# Drive.net
KiCad netlist of a schematic drawn in Altium Designer
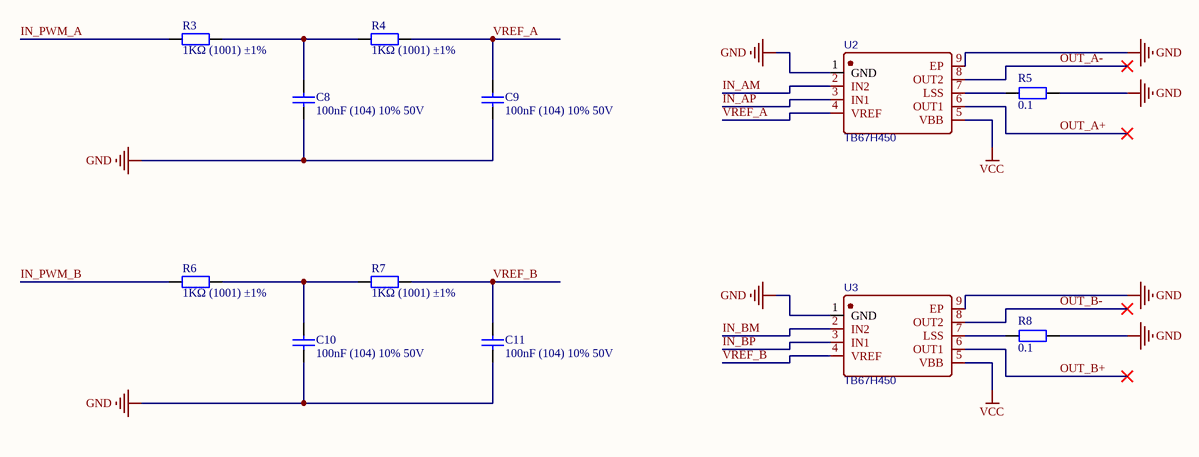
[diagram p0: Drive.SchDoc]

(export (version "E")
  (design (tool "Eeschema 10.0.6"))
  (components
    (comp (ref "C8")
      (value "100nF (104) 10% 50V")
      (footprint "0603_C")
      (description "贴片电容")
      (libsource (lib "X_Drive") (part "0603 100nF (104) 10% 50V"))
    )
    (comp (ref "C9")
      (value "100nF (104) 10% 50V")
      (footprint "0603_C")
      (description "贴片电容")
      (libsource (lib "X_Drive") (part "0603 100nF (104) 10% 50V"))
    )
    (comp (ref "C10")
      (value "100nF (104) 10% 50V")
      (footprint "0603_C")
      (description "贴片电容")
      (libsource (lib "X_Drive") (part "0603 100nF (104) 10% 50V"))
    )
    (comp (ref "C11")
      (value "100nF (104) 10% 50V")
      (footprint "0603_C")
      (description "贴片电容")
      (libsource (lib "X_Drive") (part "0603 100nF (104) 10% 50V"))
    )
    (comp (ref "R3")
      (value "1KΩ (1001) ±1%")
      (footprint "0603_R")
      (description "贴片电阻")
      (libsource (lib "X_Drive") (part "0603 1KΩ (1001) 1%"))
    )
    (comp (ref "R4")
      (value "1KΩ (1001) ±1%")
      (footprint "0603_R")
      (description "贴片电阻")
      (libsource (lib "X_Drive") (part "0603 1KΩ (1001) 1%"))
    )
    (comp (ref "R5")
      (value "0.1")
      (footprint "R0603_M")
      (description "贴片电阻")
      (fields (field (name "4.作者声明") "旨为整合最全库集,欢迎转载,禁止商用！-冰凌猫") (field (name "1.库作者") "冰凌猫"))
      (libsource (lib "0.1 - 电阻-电容-电感-磁珠-电位器") (part "R"))
    )
    (comp (ref "R6")
      (value "1KΩ (1001) ±1%")
      (footprint "0603_R")
      (description "贴片电阻")
      (libsource (lib "X_Drive") (part "0603 1KΩ (1001) 1%"))
    )
    (comp (ref "R7")
      (value "1KΩ (1001) ±1%")
      (footprint "0603_R")
      (description "贴片电阻")
      (libsource (lib "X_Drive") (part "0603 1KΩ (1001) 1%"))
    )
    (comp (ref "R8")
      (value "0.1")
      (footprint "R0603_M")
      (description "贴片电阻")
      (fields (field (name "4.作者声明") "旨为整合最全库集,欢迎转载,禁止商用！-冰凌猫") (field (name "1.库作者") "冰凌猫"))
      (libsource (lib "0.1 - 电阻-电容-电感-磁珠-电位器") (part "R"))
    )
    (comp (ref "U2")
      (value "TB67H450")
      (footprint "SOIC-8_EP_150MIL")
      (description "直流电机驱动器")
      (fields
        (field (name "BOM_MANUFACTURER PART") "A4950ELJTR-T")
        (field (name "BOM_SUPPLIER PART") "C82404")
      )
      (libsource (lib "X_Drive") (part "A4950ELJTR-T"))
    )
    (comp (ref "U3")
      (value "TB67H450")
      (footprint "SOIC-8_EP_150MIL")
      (description "直流电机驱动器")
      (fields
        (field (name "BOM_MANUFACTURER PART") "A4950ELJTR-T")
        (field (name "BOM_SUPPLIER PART") "C82404")
      )
      (libsource (lib "X_Drive") (part "A4950ELJTR-T"))
    )
  )
  (nets
    (net (code "1") (name "/IN_AM") (class "Default")
      (node (ref "U2") (pin "2") (pinfunction "IN2_2") (pintype "passive"))
    )
    (net (code "2") (name "/IN_AP") (class "Default")
      (node (ref "U2") (pin "3") (pinfunction "IN1_3") (pintype "passive"))
    )
    (net (code "3") (name "/IN_BM") (class "Default")
      (node (ref "U3") (pin "2") (pinfunction "IN2_2") (pintype "passive"))
    )
    (net (code "4") (name "/IN_BP") (class "Default")
      (node (ref "U3") (pin "3") (pinfunction "IN1_3") (pintype "passive"))
    )
    (net (code "5") (name "/IN_PWM_A") (class "Default")
      (node (ref "R3") (pin "1") (pinfunction "1_1") (pintype "passive"))
    )
    (net (code "6") (name "/IN_PWM_B") (class "Default")
      (node (ref "R6") (pin "1") (pinfunction "1_1") (pintype "passive"))
    )
    (net (code "7") (name "/OUT_A+") (class "Default")
      (node (ref "U2") (pin "6") (pinfunction "OUT1_6") (pintype "passive+no_connect"))
    )
    (net (code "8") (name "/OUT_A-") (class "Default")
      (node (ref "U2") (pin "8") (pinfunction "OUT2_8") (pintype "passive+no_connect"))
    )
    (net (code "9") (name "/OUT_B+") (class "Default")
      (node (ref "U3") (pin "6") (pinfunction "OUT1_6") (pintype "passive+no_connect"))
    )
    (net (code "10") (name "/OUT_B-") (class "Default")
      (node (ref "U3") (pin "8") (pinfunction "OUT2_8") (pintype "passive+no_connect"))
    )
    (net (code "11") (name "/VREF_A") (class "Default")
      (node (ref "C9") (pin "2") (pinfunction "2_2") (pintype "passive"))
      (node (ref "R4") (pin "2") (pinfunction "2_2") (pintype "passive"))
      (node (ref "U2") (pin "4") (pinfunction "VREF_4") (pintype "passive"))
    )
    (net (code "12") (name "/VREF_B") (class "Default")
      (node (ref "C11") (pin "2") (pinfunction "2_2") (pintype "passive"))
      (node (ref "R7") (pin "2") (pinfunction "2_2") (pintype "passive"))
      (node (ref "U3") (pin "4") (pinfunction "VREF_4") (pintype "passive"))
    )
    (net (code "13") (name "GND") (class "Default")
      (node (ref "C10") (pin "1") (pinfunction "1_1") (pintype "passive"))
      (node (ref "C11") (pin "1") (pinfunction "1_1") (pintype "passive"))
      (node (ref "C8") (pin "1") (pinfunction "1_1") (pintype "passive"))
      (node (ref "C9") (pin "1") (pinfunction "1_1") (pintype "passive"))
      (node (ref "R5") (pin "2") (pinfunction "2_2") (pintype "passive"))
      (node (ref "R8") (pin "2") (pinfunction "2_2") (pintype "passive"))
      (node (ref "U2") (pin "1") (pinfunction "GND_1") (pintype "passive"))
      (node (ref "U2") (pin "9") (pinfunction "EP_9") (pintype "passive"))
      (node (ref "U3") (pin "1") (pinfunction "GND_1") (pintype "passive"))
      (node (ref "U3") (pin "9") (pinfunction "EP_9") (pintype "passive"))
    )
    (net (code "14") (name "Net-(C8-Pad2)") (class "Default")
      (node (ref "C8") (pin "2") (pinfunction "2_2") (pintype "passive"))
      (node (ref "R3") (pin "2") (pinfunction "2_2") (pintype "passive"))
      (node (ref "R4") (pin "1") (pinfunction "1_1") (pintype "passive"))
    )
    (net (code "15") (name "Net-(C10-Pad2)") (class "Default")
      (node (ref "C10") (pin "2") (pinfunction "2_2") (pintype "passive"))
      (node (ref "R6") (pin "2") (pinfunction "2_2") (pintype "passive"))
      (node (ref "R7") (pin "1") (pinfunction "1_1") (pintype "passive"))
    )
    (net (code "16") (name "Net-(U2-LSS)") (class "Default")
      (node (ref "R5") (pin "1") (pinfunction "1_1") (pintype "passive"))
      (node (ref "U2") (pin "7") (pinfunction "LSS_7") (pintype "passive"))
    )
    (net (code "17") (name "Net-(U3-LSS)") (class "Default")
      (node (ref "R8") (pin "1") (pinfunction "1_1") (pintype "passive"))
      (node (ref "U3") (pin "7") (pinfunction "LSS_7") (pintype "passive"))
    )
    (net (code "18") (name "VCC") (class "Default")
      (node (ref "U2") (pin "5") (pinfunction "VBB_5") (pintype "passive"))
      (node (ref "U3") (pin "5") (pinfunction "VBB_5") (pintype "passive"))
    )
  )
)
